# GD25Q40ETIGR.net
KiCad netlist of a schematic drawn in EasyEDA Pro
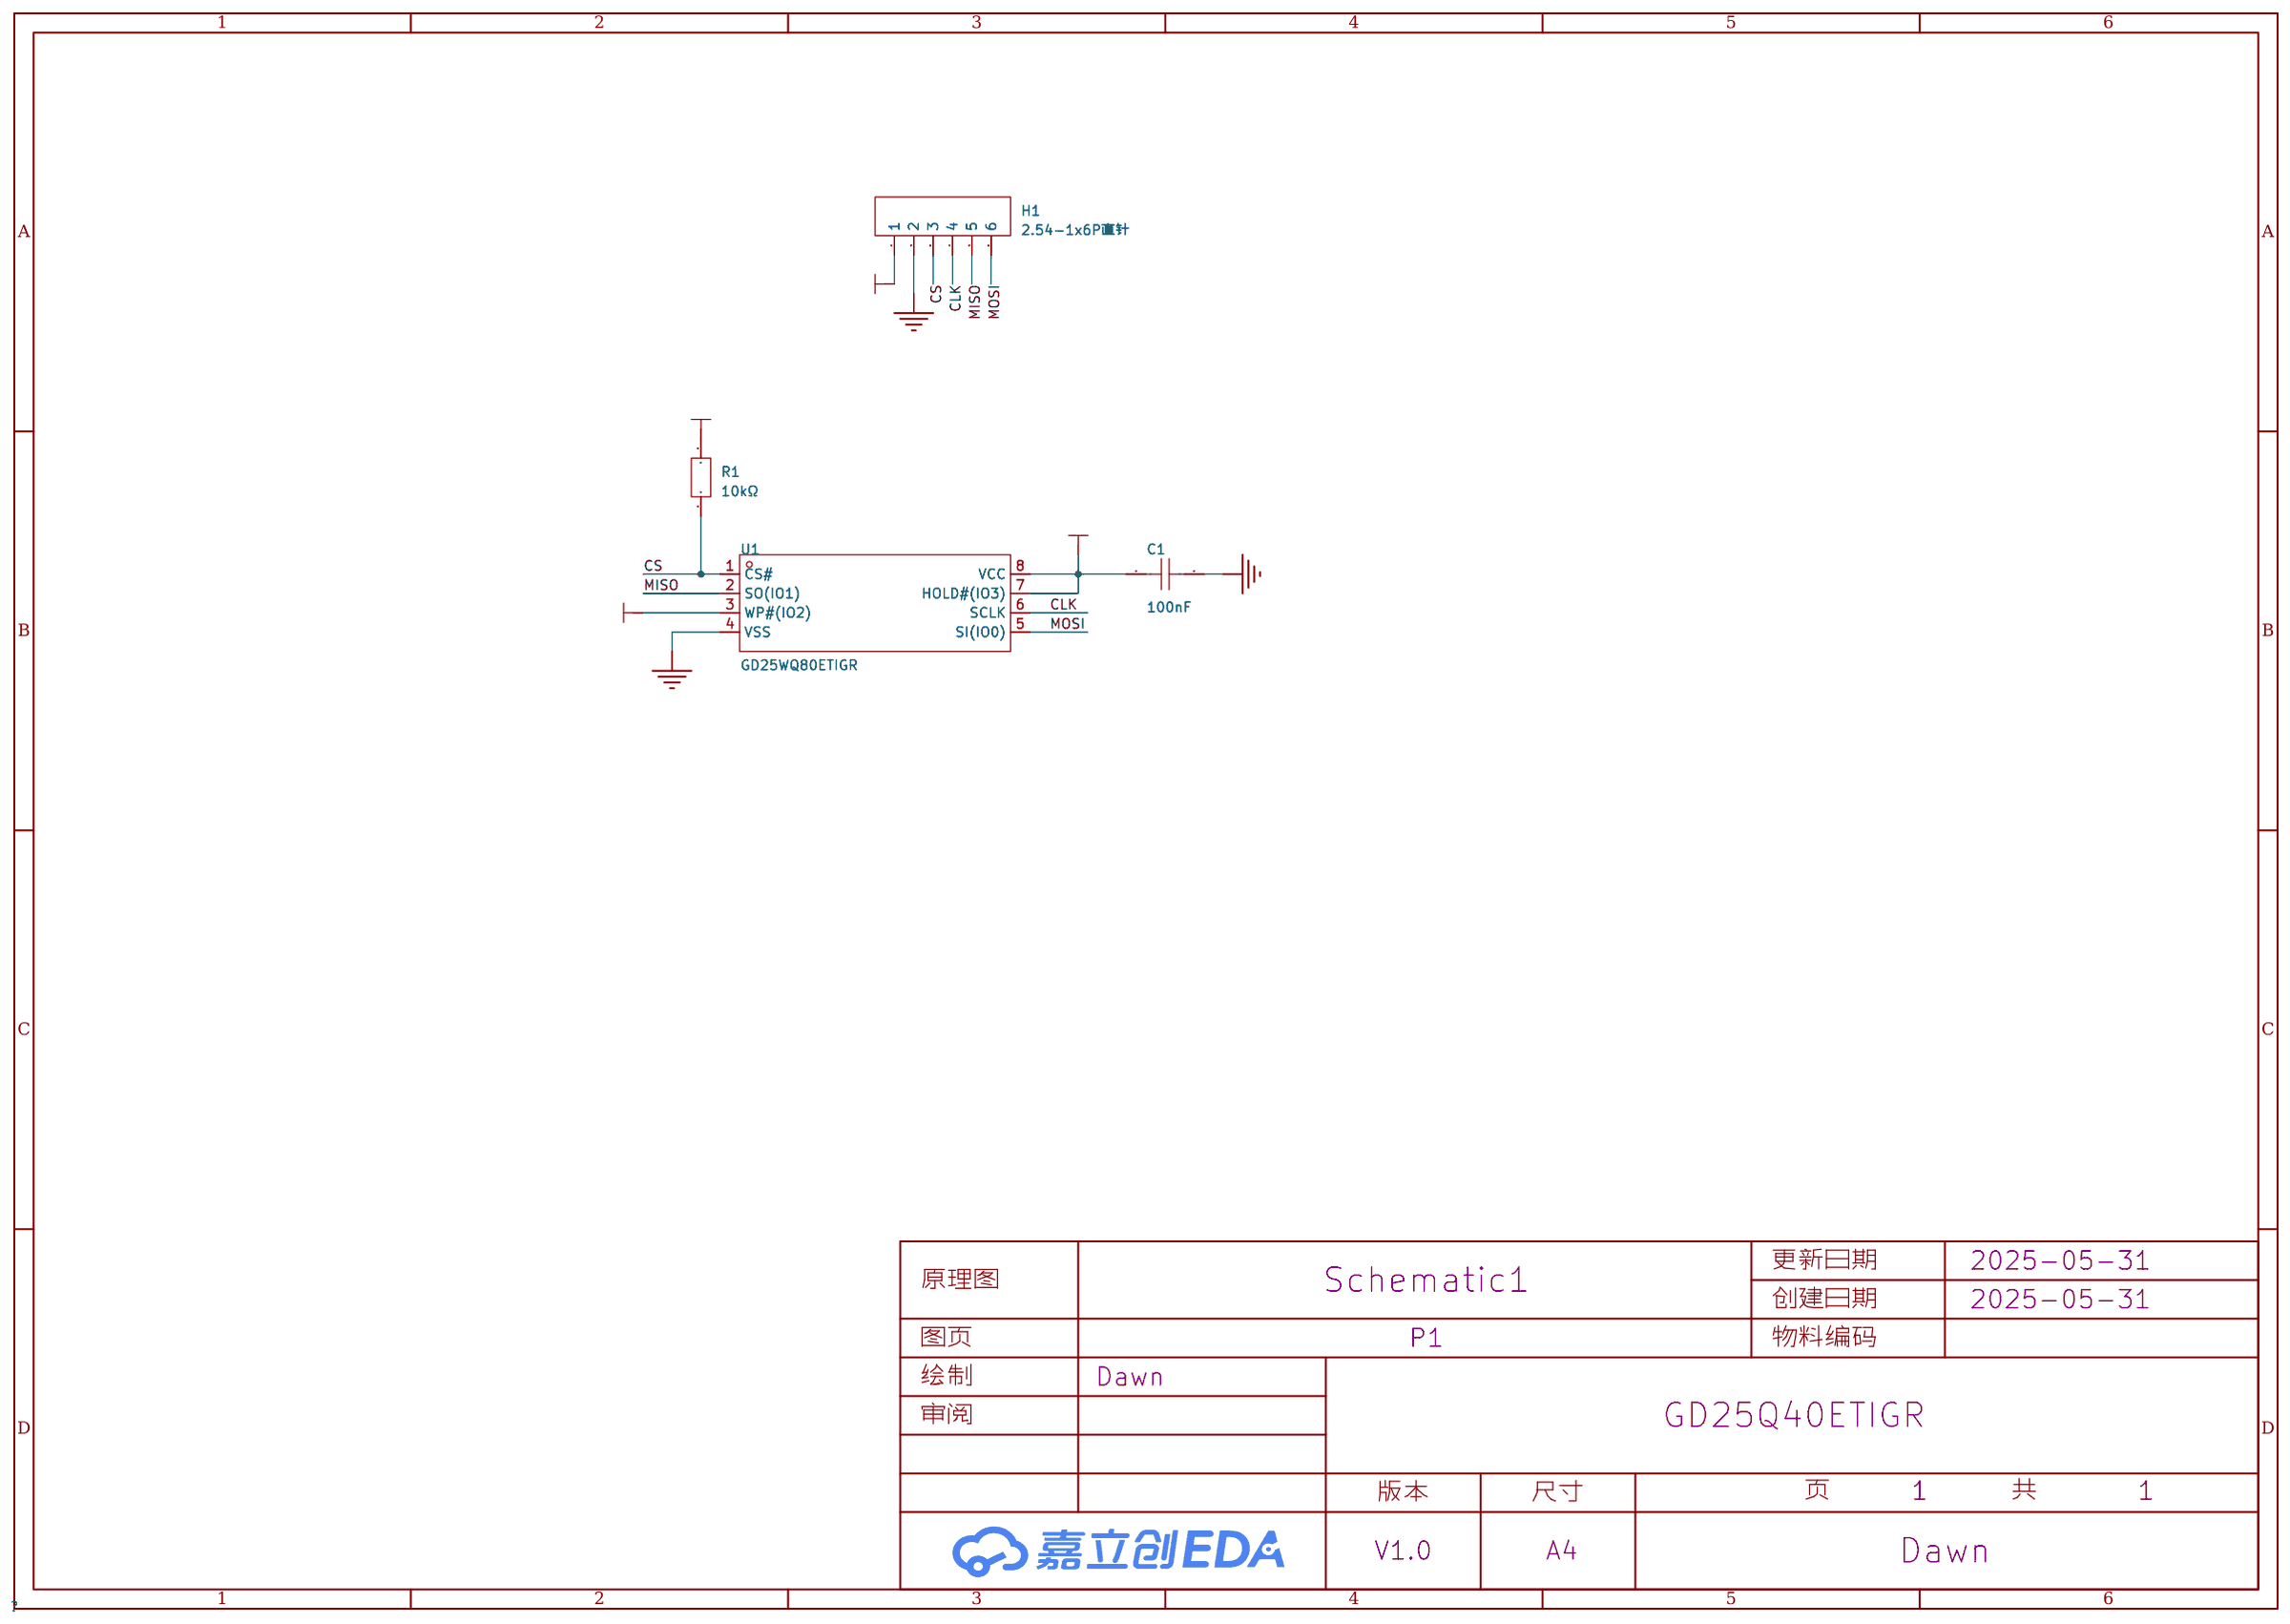
[diagram p0: schematic sheet]

(export (version "E")
  (design (tool "Eeschema 10.0.6"))
  (components
    (comp (ref "C1")
      (value "100nF")
      (footprint "easyedapro:C0603")
      (description "容值:100nF;精度:±10%;额定电压:50V;温度系数:X7R;")
      (fields
        (field (name "Manufacturer Part") "CGA0603X7R104K500JT")
        (field (name "Manufacturer") "HRE(芯声)")
      )
      (libsource (lib "easyedapro") (part "CGA0603X7R104K500JT"))
    )
    (comp (ref "H1")
      (value "2.54-1x6P直针")
      (footprint "easyedapro:HDR-TH_6P-P2.54-V-M-1")
      (fields (field (name "Manufacturer") "BOOMELE(博穆精密)"))
      (libsource (lib "easyedapro") (part "Header-Male-2.54_1x6"))
    )
    (comp (ref "R1")
      (value "10kΩ")
      (footprint "easyedapro:R0805")
      (description "阻值:10kΩ;精度:±0.1%;")
      (fields (field (name "Manufacturer Part") "AR05BTB1002") (field (name "Manufacturer") "Viking(光颉)"))
      (libsource (lib "easyedapro") (part "AR05BTB1002"))
    )
    (comp (ref "U1")
      (value "GD25WQ80ETIGR")
      (footprint "easyedapro:SOIC-8_L4.9-W3.9-P1.27-LS6.0-BL")
      (description "存储容量:8Mbit;时钟频率(fc):104MHz;")
      (fields (field (name "Manufacturer") "GigaDevice(兆易创新)"))
      (libsource (lib "easyedapro") (part "GD25WQ80ETIGR"))
    )
  )
  (nets
    (net (code "1") (name "/CLK") (class "Default")
      (node (ref "H1") (pin "4") (pinfunction "4_4") (pintype "input"))
      (node (ref "U1") (pin "6") (pinfunction "SCLK_6") (pintype "unspecified"))
    )
    (net (code "2") (name "/CS") (class "Default")
      (node (ref "H1") (pin "3") (pinfunction "3_3") (pintype "input"))
      (node (ref "R1") (pin "1") (pinfunction "1_1") (pintype "unspecified"))
      (node (ref "U1") (pin "1") (pinfunction "CS#_1") (pintype "unspecified"))
    )
    (net (code "3") (name "/MISO") (class "Default")
      (node (ref "H1") (pin "5") (pinfunction "5_5") (pintype "input"))
      (node (ref "U1") (pin "2") (pinfunction "SO(IO1)_2") (pintype "unspecified"))
    )
    (net (code "4") (name "/MOSI") (class "Default")
      (node (ref "H1") (pin "6") (pinfunction "6_6") (pintype "input"))
      (node (ref "U1") (pin "5") (pinfunction "SI(IO0)_5") (pintype "unspecified"))
    )
    (net (code "5") (name "3V3") (class "Default")
      (node (ref "C1") (pin "1") (pinfunction "1_1") (pintype "unspecified"))
      (node (ref "H1") (pin "1") (pinfunction "1_1") (pintype "input"))
      (node (ref "R1") (pin "2") (pinfunction "2_2") (pintype "unspecified"))
      (node (ref "U1") (pin "3") (pinfunction "WP#(IO2)_3") (pintype "unspecified"))
      (node (ref "U1") (pin "7") (pinfunction "HOLD#(IO3)_7") (pintype "unspecified"))
      (node (ref "U1") (pin "8") (pinfunction "VCC_8") (pintype "unspecified"))
    )
    (net (code "6") (name "GND") (class "Default")
      (node (ref "C1") (pin "2") (pinfunction "2_2") (pintype "unspecified"))
      (node (ref "H1") (pin "2") (pinfunction "2_2") (pintype "input"))
      (node (ref "U1") (pin "4") (pinfunction "VSS_4") (pintype "unspecified"))
    )
  )
)
